# bamboo-monitor.net
KiCad netlist of a schematic drawn in EAGLE
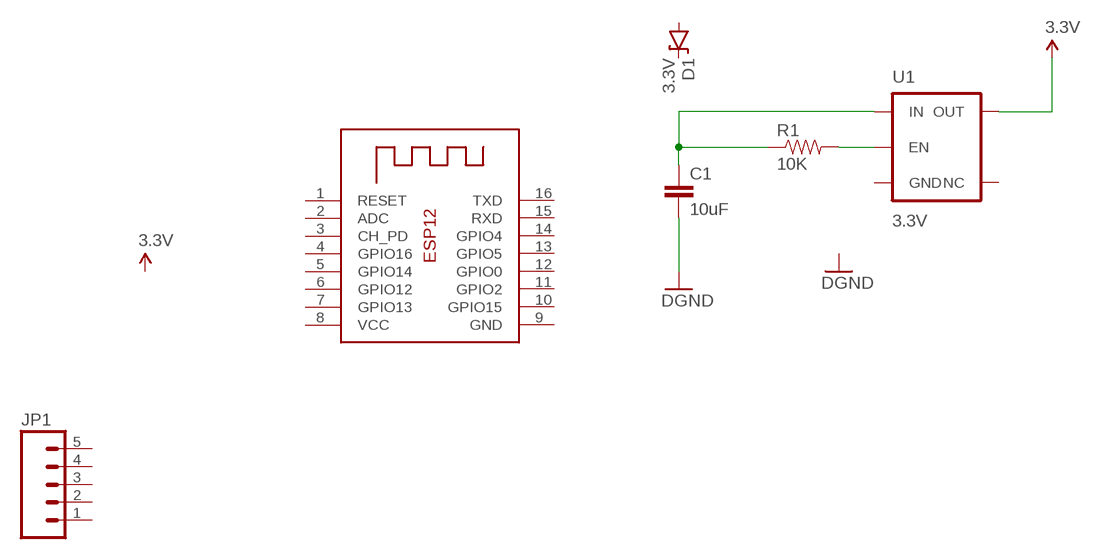
[diagram p0: schematic, sheet 1]

(export (version "E")
  (design (tool "Eeschema 10.0.6"))
  (components
    (comp (ref "C1")
      (value "10uF")
      (footprint "eagle-import:0603-CAP")
      (libsource (lib "eagle-import") (part "10UF-6.3V-20%(0603)"))
    )
    (comp (ref "D1")
      (value "3.3V")
      (footprint "eagle-import:SOD-323")
      (libsource (lib "eagle-import") (part "DIODE-ZENER3.3V"))
    )
    (comp (ref "JP1")
      (value "M05PTH")
      (footprint "eagle-import:1X05")
      (libsource (lib "eagle-import") (part "M05PTH"))
    )
    (comp (ref "R1")
      (value "10K")
      (footprint "eagle-import:0603-RES")
      (libsource (lib "eagle-import") (part "10KOHM-1/10W-1%(0603)0603"))
    )
    (comp (ref "U1")
      (value "3.3V")
      (footprint "eagle-import:SOT23-5")
      (libsource (lib "eagle-import") (part "V_REG_AP2112K-3.3V"))
    )
    (comp (ref "X1")
      (value "ESP-12")
      (footprint "eagle-import:ESP-12")
      (libsource (lib "eagle-import") (part "ESP-12"))
    )
  )
  (nets
    (net (code "1") (name "/GND") (class "Default")
      (node (ref "X1") (pin "9") (pinfunction "GND_9") (pintype "power_in"))
    )
    (net (code "2") (name "/VCC") (class "Default")
      (node (ref "X1") (pin "8") (pinfunction "VCC_8") (pintype "power_in"))
    )
    (net (code "3") (name "3.3V") (class "Default")
      (node (ref "U1") (pin "5") (pinfunction "OUT_5") (pintype "passive"))
    )
    (net (code "4") (name "DGND") (class "Default")
      (node (ref "C1") (pin "2") (pinfunction "2_2") (pintype "passive"))
    )
    (net (code "5") (name "Net-(U1-EN)") (class "Default")
      (node (ref "R1") (pin "2") (pinfunction "2_2") (pintype "passive"))
      (node (ref "U1") (pin "3") (pinfunction "EN_3") (pintype "input"))
    )
    (net (code "6") (name "Net-(U1-IN)") (class "Default")
      (node (ref "C1") (pin "1") (pinfunction "1_1") (pintype "passive"))
      (node (ref "R1") (pin "1") (pinfunction "1_1") (pintype "passive"))
      (node (ref "U1") (pin "1") (pinfunction "IN_1") (pintype "input"))
    )
    (net (code "7") (name "unconnected-(D1-PadA)") (class "Default")
      (node (ref "D1") (pin "A") (pinfunction "A_A") (pintype "passive"))
    )
    (net (code "8") (name "unconnected-(D1-PadC)") (class "Default")
      (node (ref "D1") (pin "C") (pinfunction "C_C") (pintype "passive"))
    )
    (net (code "9") (name "unconnected-(JP1-Pad1)") (class "Default")
      (node (ref "JP1") (pin "1") (pinfunction "1_1") (pintype "passive"))
    )
    (net (code "10") (name "unconnected-(JP1-Pad2)") (class "Default")
      (node (ref "JP1") (pin "2") (pinfunction "2_2") (pintype "passive"))
    )
    (net (code "11") (name "unconnected-(JP1-Pad3)") (class "Default")
      (node (ref "JP1") (pin "3") (pinfunction "3_3") (pintype "passive"))
    )
    (net (code "12") (name "unconnected-(JP1-Pad4)") (class "Default")
      (node (ref "JP1") (pin "4") (pinfunction "4_4") (pintype "passive"))
    )
    (net (code "13") (name "unconnected-(JP1-Pad5)") (class "Default")
      (node (ref "JP1") (pin "5") (pinfunction "5_5") (pintype "passive"))
    )
    (net (code "14") (name "unconnected-(U1-GND-Pad2)") (class "Default")
      (node (ref "U1") (pin "2") (pinfunction "GND_2") (pintype "input"))
    )
    (net (code "15") (name "unconnected-(U1-NC-Pad4)") (class "Default")
      (node (ref "U1") (pin "4") (pinfunction "NC_4") (pintype "input"))
    )
    (net (code "16") (name "unconnected-(X1-ADC-Pad2)") (class "Default")
      (node (ref "X1") (pin "2") (pinfunction "ADC_2") (pintype "passive"))
    )
    (net (code "17") (name "unconnected-(X1-CH_PD-Pad3)") (class "Default")
      (node (ref "X1") (pin "3") (pinfunction "CH_PD_3") (pintype "input"))
    )
    (net (code "18") (name "unconnected-(X1-GPIO0-Pad12)") (class "Default")
      (node (ref "X1") (pin "12") (pinfunction "GPIO0_12") (pintype "bidirectional"))
    )
    (net (code "19") (name "unconnected-(X1-GPIO2-Pad11)") (class "Default")
      (node (ref "X1") (pin "11") (pinfunction "GPIO2_11") (pintype "bidirectional"))
    )
    (net (code "20") (name "unconnected-(X1-GPIO4-Pad14)") (class "Default")
      (node (ref "X1") (pin "14") (pinfunction "GPIO4_14") (pintype "bidirectional"))
    )
    (net (code "21") (name "unconnected-(X1-GPIO5-Pad13)") (class "Default")
      (node (ref "X1") (pin "13") (pinfunction "GPIO5_13") (pintype "bidirectional"))
    )
    (net (code "22") (name "unconnected-(X1-GPIO12-Pad6)") (class "Default")
      (node (ref "X1") (pin "6") (pinfunction "GPIO12_6") (pintype "bidirectional"))
    )
    (net (code "23") (name "unconnected-(X1-GPIO13-Pad7)") (class "Default")
      (node (ref "X1") (pin "7") (pinfunction "GPIO13_7") (pintype "bidirectional"))
    )
    (net (code "24") (name "unconnected-(X1-GPIO14-Pad5)") (class "Default")
      (node (ref "X1") (pin "5") (pinfunction "GPIO14_5") (pintype "bidirectional"))
    )
    (net (code "25") (name "unconnected-(X1-GPIO15-Pad10)") (class "Default")
      (node (ref "X1") (pin "10") (pinfunction "GPIO15_10") (pintype "bidirectional"))
    )
    (net (code "26") (name "unconnected-(X1-GPIO16-Pad4)") (class "Default")
      (node (ref "X1") (pin "4") (pinfunction "GPIO16_4") (pintype "bidirectional"))
    )
    (net (code "27") (name "unconnected-(X1-RESET-Pad1)") (class "Default")
      (node (ref "X1") (pin "1") (pinfunction "RESET_1") (pintype "input"))
    )
    (net (code "28") (name "unconnected-(X1-RXD-Pad15)") (class "Default")
      (node (ref "X1") (pin "15") (pinfunction "RXD_15") (pintype "input"))
    )
    (net (code "29") (name "unconnected-(X1-TXD-Pad16)") (class "Default")
      (node (ref "X1") (pin "16") (pinfunction "TXD_16") (pintype "output"))
    )
  )
)
